# SpeakEasy_Buck.net
KiCad netlist of a schematic drawn in Altium Designer
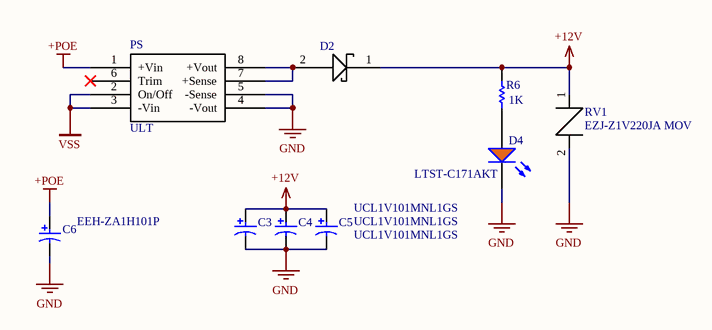
[diagram p0: SpeakEasy_Buck.SchDoc]

(export (version "E")
  (design (tool "Eeschema 10.0.6"))
  (components
    (comp (ref "C3")
      (value "UCL1V101MNL1GS")
      (footprint "NIC-UCL1V101MNL1GS_L")
      (fields (field (name "MANUFACTURER") "Nichicon") (field (name "TOLERANCE") "20%"))
      (libsource (lib "Altium Content Vault") (part "CAP-P-2"))
    )
    (comp (ref "C4")
      (value "UCL1V101MNL1GS")
      (footprint "NIC-UCL1V101MNL1GS_L")
      (fields (field (name "MANUFACTURER") "Nichicon") (field (name "TOLERANCE") "20%"))
      (libsource (lib "Altium Content Vault") (part "CAP-P-2"))
    )
    (comp (ref "C5")
      (value "UCL1V101MNL1GS")
      (footprint "NIC-UCL1V101MNL1GS_L")
      (fields (field (name "MANUFACTURER") "Nichicon") (field (name "TOLERANCE") "20%"))
      (libsource (lib "Altium Content Vault") (part "CAP-P-2"))
    )
    (comp (ref "C6")
      (value "EEH-ZA1H101P")
      (footprint "PNSC-ZA-G_L")
      (fields (field (name "TOLERANCE") "20%") (field (name "MANUFACTURER") "Panasonic"))
      (libsource (lib "Altium Content Vault") (part "CAP-P-2"))
    )
    (comp (ref "D2")
      (value "Shottkey Diode")
      (footprint "DO-220AA")
      (libsource (lib "SpeakEasy") (part "V3P6"))
    )
    (comp (ref "D4")
      (value "LTST-C171AKT")
      (footprint "LTST-C171AKT_V")
      (description "LED AMBER CLR THIN 0805 SMD")
      (fields (field (name "MANUFACTURER") "Lite-On"))
      (libsource (lib "Altium Content Vault") (part "LED_AMBER_AC"))
    )
    (comp (ref "PS")
      (value "ULT")
      (footprint "ULT-12/2.5")
      (description "+12V/2.5A DC/DC Converter, requires 36-75V input to power on.")
      (libsource (lib "SpeakEasy") (part "ULT"))
    )
    (comp (ref "R6")
      (value "1K")
      (footprint "RESC0603(1608)_N")
      (fields (field (name "TOLERANCE") "5 %") (field (name "POWER") "0.1 W") (field (name "Comment") "1k"))
      (libsource (lib "Altium Content Vault") (part "RES"))
    )
    (comp (ref "RV1")
      (value "EZJ-Z1V220JA MOV")
      (footprint "DIOC1608X06N")
      (description "Voltage Supression")
      (libsource (lib "SE_Lib") (part "EZJ-Z1V220JA"))
    )
  )
  (nets
    (net (code "1") (name "+12V") (class "Default")
      (node (ref "C3") (pin "1") (pinfunction "1_1") (pintype "passive"))
      (node (ref "C4") (pin "1") (pinfunction "1_1") (pintype "passive"))
      (node (ref "C5") (pin "1") (pinfunction "1_1") (pintype "passive"))
      (node (ref "D2") (pin "1") (pinfunction "-_1") (pintype "passive"))
      (node (ref "R6") (pin "2") (pinfunction "2_2") (pintype "passive"))
      (node (ref "RV1") (pin "1") (pinfunction "1_1") (pintype "passive"))
    )
    (net (code "2") (name "+POE") (class "Default")
      (node (ref "C6") (pin "1") (pinfunction "1_1") (pintype "passive"))
      (node (ref "PS") (pin "1") (pinfunction "+Vin_1") (pintype "passive"))
    )
    (net (code "3") (name "GND") (class "Default")
      (node (ref "C3") (pin "2") (pinfunction "2_2") (pintype "passive"))
      (node (ref "C4") (pin "2") (pinfunction "2_2") (pintype "passive"))
      (node (ref "C5") (pin "2") (pinfunction "2_2") (pintype "passive"))
      (node (ref "C6") (pin "2") (pinfunction "2_2") (pintype "passive"))
      (node (ref "D4") (pin "C") (pinfunction "C_C") (pintype "passive"))
      (node (ref "PS") (pin "4") (pinfunction "-Vout_4") (pintype "passive"))
      (node (ref "PS") (pin "5") (pinfunction "-Sense_5") (pintype "passive"))
      (node (ref "RV1") (pin "2") (pinfunction "2_2") (pintype "passive"))
    )
    (net (code "4") (name "Net-(D2-+)") (class "Default")
      (node (ref "D2") (pin "2") (pinfunction "+_2") (pintype "passive"))
      (node (ref "PS") (pin "7") (pinfunction "+Sense_7") (pintype "passive"))
      (node (ref "PS") (pin "8") (pinfunction "+Vout_8") (pintype "passive"))
    )
    (net (code "5") (name "Net-(D4-PadA)") (class "Default")
      (node (ref "D4") (pin "A") (pinfunction "A_A") (pintype "passive"))
      (node (ref "R6") (pin "1") (pinfunction "1_1") (pintype "passive"))
    )
    (net (code "6") (name "VSS") (class "Default")
      (node (ref "PS") (pin "2") (pinfunction "On/Off_2") (pintype "passive"))
      (node (ref "PS") (pin "3") (pinfunction "-Vin_3") (pintype "passive"))
    )
    (net (code "7") (name "unconnected-(PS-Trim-Pad6)") (class "Default")
      (node (ref "PS") (pin "6") (pinfunction "Trim_6") (pintype "passive+no_connect"))
    )
  )
)
